# Sheet1.net
KiCad netlist of a schematic drawn in Altium Designer
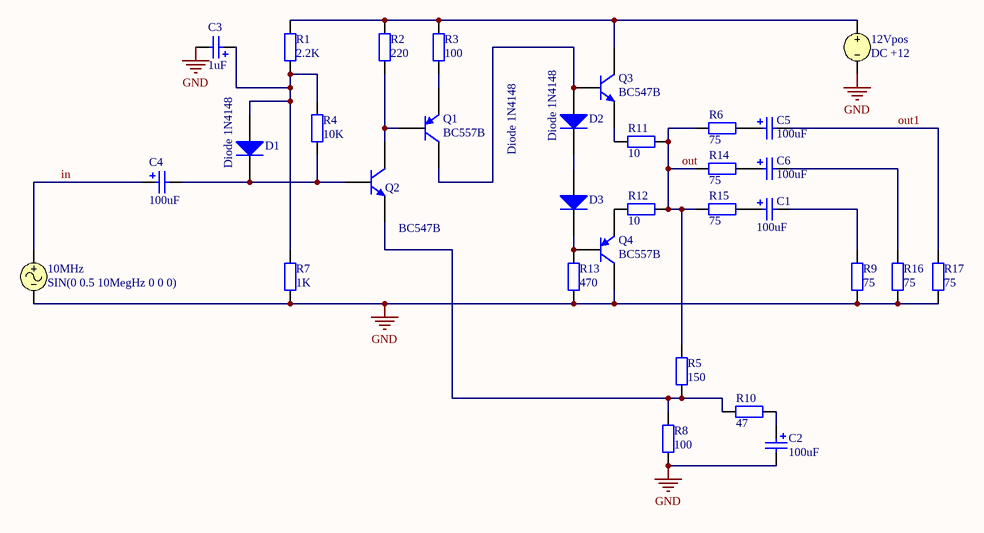
[diagram p0: Sheet1.SchDoc]

(export (version "E")
  (design (tool "Eeschema 10.0.6"))
  (components
    (comp (ref "10MHz")
      (value "SIN(0 0.5 10MegHz 0 0 0)")
      (description "Sinusoidal Voltage Source")
      (fields (field (name "PUBLISHER") "Altium Limited"))
      (libsource (lib "Simulation Generic Components") (part "VSIN"))
    )
    (comp (ref "12Vpos")
      (value "DC +12")
      (description "Voltage Source")
      (fields (field (name "PUBLISHER") "Altium Limited"))
      (libsource (lib "Simulation Generic Components") (part "VSRC"))
    )
    (comp (ref "C1")
      (value "100uF")
      (footprint "POLAR0.8")
      (description "Polarized Capacitor (Axial)")
      (fields (field (name "Comment") "Cap Pol2") (field (name "PUBLISHER") "Altium Limited"))
      (libsource (lib "Miscellaneous Devices") (part "Cap Pol2"))
    )
    (comp (ref "C2")
      (value "100uF")
      (footprint "POLAR0.8")
      (description "Polarized Capacitor (Axial)")
      (fields (field (name "Comment") "Cap Pol2") (field (name "PUBLISHER") "Altium Limited"))
      (libsource (lib "Miscellaneous Devices") (part "Cap Pol2"))
    )
    (comp (ref "C3")
      (value "1uF")
      (footprint "POLAR0.8")
      (description "Polarized Capacitor (Axial)")
      (fields (field (name "Comment") "Cap Pol2") (field (name "PUBLISHER") "Altium Limited"))
      (libsource (lib "Miscellaneous Devices") (part "Cap Pol2"))
    )
    (comp (ref "C4")
      (value "100uF")
      (footprint "POLAR0.8")
      (description "Polarized Capacitor (Axial)")
      (fields (field (name "Comment") "Cap Pol2") (field (name "PUBLISHER") "Altium Limited"))
      (libsource (lib "Miscellaneous Devices") (part "Cap Pol2"))
    )
    (comp (ref "C5")
      (value "100uF")
      (footprint "POLAR0.8")
      (description "Polarized Capacitor (Axial)")
      (fields (field (name "Comment") "Cap Pol2") (field (name "PUBLISHER") "Altium Limited"))
      (libsource (lib "Miscellaneous Devices") (part "Cap Pol2"))
    )
    (comp (ref "C6")
      (value "100uF")
      (footprint "POLAR0.8")
      (description "Polarized Capacitor (Axial)")
      (fields (field (name "Comment") "Cap Pol2") (field (name "PUBLISHER") "Altium Limited"))
      (libsource (lib "Miscellaneous Devices") (part "Cap Pol2"))
    )
    (comp (ref "D1")
      (value "Diode 1N4148")
      (footprint "DO-35")
      (description "High Conductance Fast Diode")
      (fields (field (name "PUBLISHER") "Altium Limited"))
      (libsource (lib "Miscellaneous Devices") (part "Diode 1N4148"))
    )
    (comp (ref "D2")
      (value "Diode 1N4148")
      (footprint "DO-35")
      (description "High Conductance Fast Diode")
      (fields (field (name "PUBLISHER") "Altium Limited"))
      (libsource (lib "Miscellaneous Devices") (part "Diode 1N4148"))
    )
    (comp (ref "D3")
      (value "Diode 1N4148")
      (footprint "DO-35")
      (description "High Conductance Fast Diode")
      (fields (field (name "PUBLISHER") "Altium Limited"))
      (libsource (lib "Miscellaneous Devices") (part "Diode 1N4148"))
    )
    (comp (ref "Q1")
      (value "BC557B")
      (footprint "SOT54")
      (description "PNP General-purpose Transistor")
      (fields (field (name "PUBLISHER") "Altium Limited"))
      (libsource (lib "Philips Discrete BJT - Low Power") (part "BC557B"))
    )
    (comp (ref "Q2")
      (value "BC547B")
      (footprint "SOT54")
      (description "NPN General-purpose Transistor")
      (fields (field (name "PUBLISHER") "Altium Limited"))
      (libsource (lib "Philips Discrete BJT - Low Power") (part "BC547B"))
    )
    (comp (ref "Q3")
      (value "BC547B")
      (footprint "SOT54")
      (description "NPN General-purpose Transistor")
      (fields (field (name "PUBLISHER") "Altium Limited"))
      (libsource (lib "Philips Discrete BJT - Low Power") (part "BC547B"))
    )
    (comp (ref "Q4")
      (value "BC557B")
      (footprint "SOT54")
      (description "PNP General-purpose Transistor")
      (fields (field (name "PUBLISHER") "Altium Limited"))
      (libsource (lib "Philips Discrete BJT - Low Power") (part "BC557B"))
    )
    (comp (ref "R1")
      (value "2.2K")
      (footprint "AXIAL-0.4")
      (description "Resistor")
      (fields (field (name "Comment") "Res2") (field (name "PUBLISHER") "Altium Limited"))
      (libsource (lib "Miscellaneous Devices") (part "Res2"))
    )
    (comp (ref "R2")
      (value "220")
      (footprint "AXIAL-0.4")
      (description "Resistor")
      (fields (field (name "Comment") "Res2") (field (name "PUBLISHER") "Altium Limited"))
      (libsource (lib "Miscellaneous Devices") (part "Res2"))
    )
    (comp (ref "R3")
      (value "100")
      (footprint "AXIAL-0.4")
      (description "Resistor")
      (fields (field (name "Comment") "Res2") (field (name "PUBLISHER") "Altium Limited"))
      (libsource (lib "Miscellaneous Devices") (part "Res2"))
    )
    (comp (ref "R4")
      (value "10K")
      (footprint "AXIAL-0.4")
      (description "Resistor")
      (fields (field (name "Comment") "Res2") (field (name "PUBLISHER") "Altium Limited"))
      (libsource (lib "Miscellaneous Devices") (part "Res2"))
    )
    (comp (ref "R5")
      (value "150")
      (footprint "AXIAL-0.4")
      (description "Resistor")
      (fields (field (name "Comment") "Res2") (field (name "PUBLISHER") "Altium Limited"))
      (libsource (lib "Miscellaneous Devices") (part "Res2"))
    )
    (comp (ref "R6")
      (value "75")
      (footprint "AXIAL-0.4")
      (description "Resistor")
      (fields (field (name "Comment") "Res2") (field (name "PUBLISHER") "Altium Limited"))
      (libsource (lib "") (part "Res2_1"))
    )
    (comp (ref "R7")
      (value "1K")
      (footprint "AXIAL-0.4")
      (description "Resistor")
      (fields (field (name "Comment") "Res2") (field (name "PUBLISHER") "Altium Limited"))
      (libsource (lib "Miscellaneous Devices") (part "Res2"))
    )
    (comp (ref "R8")
      (value "100")
      (footprint "AXIAL-0.4")
      (description "Resistor")
      (fields (field (name "Comment") "Res2") (field (name "PUBLISHER") "Altium Limited"))
      (libsource (lib "Miscellaneous Devices") (part "Res2"))
    )
    (comp (ref "R9")
      (value "75")
      (footprint "AXIAL-0.4")
      (description "Resistor")
      (fields (field (name "Comment") "Res2") (field (name "PUBLISHER") "Altium Limited"))
      (libsource (lib "Miscellaneous Devices") (part "Res2"))
    )
    (comp (ref "R10")
      (value "47")
      (footprint "AXIAL-0.4")
      (description "Resistor")
      (fields (field (name "Comment") "Res2") (field (name "PUBLISHER") "Altium Limited"))
      (libsource (lib "") (part "Res2_1"))
    )
    (comp (ref "R11")
      (value "10")
      (footprint "AXIAL-0.4")
      (description "Resistor")
      (fields (field (name "Comment") "Res2") (field (name "PUBLISHER") "Altium Limited"))
      (libsource (lib "") (part "Res2_1"))
    )
    (comp (ref "R12")
      (value "10")
      (footprint "AXIAL-0.4")
      (description "Resistor")
      (fields (field (name "Comment") "Res2") (field (name "PUBLISHER") "Altium Limited"))
      (libsource (lib "") (part "Res2_1"))
    )
    (comp (ref "R13")
      (value "470")
      (footprint "AXIAL-0.4")
      (description "Resistor")
      (fields (field (name "Comment") "Res2") (field (name "PUBLISHER") "Altium Limited"))
      (libsource (lib "Miscellaneous Devices") (part "Res2"))
    )
    (comp (ref "R14")
      (value "75")
      (footprint "AXIAL-0.4")
      (description "Resistor")
      (fields (field (name "Comment") "Res2") (field (name "PUBLISHER") "Altium Limited"))
      (libsource (lib "") (part "Res2_1"))
    )
    (comp (ref "R15")
      (value "75")
      (footprint "AXIAL-0.4")
      (description "Resistor")
      (fields (field (name "Comment") "Res2") (field (name "PUBLISHER") "Altium Limited"))
      (libsource (lib "") (part "Res2_1"))
    )
    (comp (ref "R16")
      (value "75")
      (footprint "AXIAL-0.4")
      (description "Resistor")
      (fields (field (name "Comment") "Res2") (field (name "PUBLISHER") "Altium Limited"))
      (libsource (lib "Miscellaneous Devices") (part "Res2"))
    )
    (comp (ref "R17")
      (value "75")
      (footprint "AXIAL-0.4")
      (description "Resistor")
      (fields (field (name "Comment") "Res2") (field (name "PUBLISHER") "Altium Limited"))
      (libsource (lib "Miscellaneous Devices") (part "Res2"))
    )
  )
  (nets
    (net (code "1") (name "/in") (class "Default")
      (node (ref "10MHz") (pin "1") (pinfunction "1_1") (pintype "passive"))
      (node (ref "C4") (pin "1") (pinfunction "1_1") (pintype "passive"))
    )
    (net (code "2") (name "/out") (class "Default")
      (node (ref "R11") (pin "1") (pinfunction "1_1") (pintype "passive"))
      (node (ref "R12") (pin "1") (pinfunction "1_1") (pintype "passive"))
      (node (ref "R14") (pin "2") (pinfunction "2_2") (pintype "passive"))
      (node (ref "R15") (pin "2") (pinfunction "2_2") (pintype "passive"))
      (node (ref "R5") (pin "2") (pinfunction "2_2") (pintype "passive"))
      (node (ref "R6") (pin "2") (pinfunction "2_2") (pintype "passive"))
    )
    (net (code "3") (name "/out1") (class "Default")
      (node (ref "C5") (pin "2") (pinfunction "2_2") (pintype "passive"))
      (node (ref "R17") (pin "2") (pinfunction "2_2") (pintype "passive"))
    )
    (net (code "4") (name "GND") (class "Default")
      (node (ref "10MHz") (pin "2") (pinfunction "2_2") (pintype "passive"))
      (node (ref "12Vpos") (pin "2") (pinfunction "2_2") (pintype "passive"))
      (node (ref "C2") (pin "2") (pinfunction "2_2") (pintype "passive"))
      (node (ref "C3") (pin "2") (pinfunction "2_2") (pintype "passive"))
      (node (ref "Q4") (pin "3") (pinfunction "C_3") (pintype "passive"))
      (node (ref "R13") (pin "1") (pinfunction "1_1") (pintype "passive"))
      (node (ref "R16") (pin "1") (pinfunction "1_1") (pintype "passive"))
      (node (ref "R17") (pin "1") (pinfunction "1_1") (pintype "passive"))
      (node (ref "R7") (pin "1") (pinfunction "1_1") (pintype "passive"))
      (node (ref "R8") (pin "1") (pinfunction "1_1") (pintype "passive"))
      (node (ref "R9") (pin "1") (pinfunction "1_1") (pintype "passive"))
    )
    (net (code "5") (name "Net-(C1-Pad1)") (class "Default")
      (node (ref "C1") (pin "1") (pinfunction "1_1") (pintype "passive"))
      (node (ref "R15") (pin "1") (pinfunction "1_1") (pintype "passive"))
    )
    (net (code "6") (name "Net-(C1-Pad2)") (class "Default")
      (node (ref "C1") (pin "2") (pinfunction "2_2") (pintype "passive"))
      (node (ref "R9") (pin "2") (pinfunction "2_2") (pintype "passive"))
    )
    (net (code "7") (name "Net-(C2-Pad1)") (class "Default")
      (node (ref "C2") (pin "1") (pinfunction "1_1") (pintype "passive"))
      (node (ref "R10") (pin "1") (pinfunction "1_1") (pintype "passive"))
    )
    (net (code "8") (name "Net-(C5-Pad1)") (class "Default")
      (node (ref "C5") (pin "1") (pinfunction "1_1") (pintype "passive"))
      (node (ref "R6") (pin "1") (pinfunction "1_1") (pintype "passive"))
    )
    (net (code "9") (name "Net-(C6-Pad1)") (class "Default")
      (node (ref "C6") (pin "1") (pinfunction "1_1") (pintype "passive"))
      (node (ref "R14") (pin "1") (pinfunction "1_1") (pintype "passive"))
    )
    (net (code "10") (name "Net-(C6-Pad2)") (class "Default")
      (node (ref "C6") (pin "2") (pinfunction "2_2") (pintype "passive"))
      (node (ref "R16") (pin "2") (pinfunction "2_2") (pintype "passive"))
    )
    (net (code "11") (name "Net-(D1-A)") (class "Default")
      (node (ref "C3") (pin "1") (pinfunction "1_1") (pintype "passive"))
      (node (ref "D1") (pin "1") (pinfunction "A_1") (pintype "passive"))
      (node (ref "R1") (pin "1") (pinfunction "1_1") (pintype "passive"))
      (node (ref "R4") (pin "2") (pinfunction "2_2") (pintype "passive"))
      (node (ref "R7") (pin "2") (pinfunction "2_2") (pintype "passive"))
    )
    (net (code "12") (name "Net-(D1-K)") (class "Default")
      (node (ref "C4") (pin "2") (pinfunction "2_2") (pintype "passive"))
      (node (ref "D1") (pin "2") (pinfunction "K_2") (pintype "passive"))
      (node (ref "Q2") (pin "2") (pinfunction "B_2") (pintype "passive"))
      (node (ref "R4") (pin "1") (pinfunction "1_1") (pintype "passive"))
    )
    (net (code "13") (name "Net-(D2-A)") (class "Default")
      (node (ref "D2") (pin "1") (pinfunction "A_1") (pintype "passive"))
      (node (ref "Q1") (pin "3") (pinfunction "C_3") (pintype "passive"))
      (node (ref "Q3") (pin "2") (pinfunction "B_2") (pintype "passive"))
    )
    (net (code "14") (name "Net-(D2-K)") (class "Default")
      (node (ref "D2") (pin "2") (pinfunction "K_2") (pintype "passive"))
      (node (ref "D3") (pin "1") (pinfunction "A_1") (pintype "passive"))
    )
    (net (code "15") (name "Net-(D3-K)") (class "Default")
      (node (ref "D3") (pin "2") (pinfunction "K_2") (pintype "passive"))
      (node (ref "Q4") (pin "2") (pinfunction "B_2") (pintype "passive"))
      (node (ref "R13") (pin "2") (pinfunction "2_2") (pintype "passive"))
    )
    (net (code "16") (name "Net-(Q1-B)") (class "Default")
      (node (ref "Q1") (pin "2") (pinfunction "B_2") (pintype "passive"))
      (node (ref "Q2") (pin "3") (pinfunction "C_3") (pintype "passive"))
      (node (ref "R2") (pin "1") (pinfunction "1_1") (pintype "passive"))
    )
    (net (code "17") (name "Net-(Q1-E)") (class "Default")
      (node (ref "Q1") (pin "1") (pinfunction "E_1") (pintype "passive"))
      (node (ref "R3") (pin "1") (pinfunction "1_1") (pintype "passive"))
    )
    (net (code "18") (name "Net-(Q2-E)") (class "Default")
      (node (ref "Q2") (pin "1") (pinfunction "E_1") (pintype "passive"))
      (node (ref "R10") (pin "2") (pinfunction "2_2") (pintype "passive"))
      (node (ref "R5") (pin "1") (pinfunction "1_1") (pintype "passive"))
      (node (ref "R8") (pin "2") (pinfunction "2_2") (pintype "passive"))
    )
    (net (code "19") (name "Net-(Q3-C)") (class "Default")
      (node (ref "12Vpos") (pin "1") (pinfunction "1_1") (pintype "passive"))
      (node (ref "Q3") (pin "3") (pinfunction "C_3") (pintype "passive"))
      (node (ref "R1") (pin "2") (pinfunction "2_2") (pintype "passive"))
      (node (ref "R2") (pin "2") (pinfunction "2_2") (pintype "passive"))
      (node (ref "R3") (pin "2") (pinfunction "2_2") (pintype "passive"))
    )
    (net (code "20") (name "Net-(Q3-E)") (class "Default")
      (node (ref "Q3") (pin "1") (pinfunction "E_1") (pintype "passive"))
      (node (ref "R11") (pin "2") (pinfunction "2_2") (pintype "passive"))
    )
    (net (code "21") (name "Net-(Q4-E)") (class "Default")
      (node (ref "Q4") (pin "1") (pinfunction "E_1") (pintype "passive"))
      (node (ref "R12") (pin "2") (pinfunction "2_2") (pintype "passive"))
    )
  )
)
